# Design.net
KiCad netlist of a schematic drawn in EasyEDA
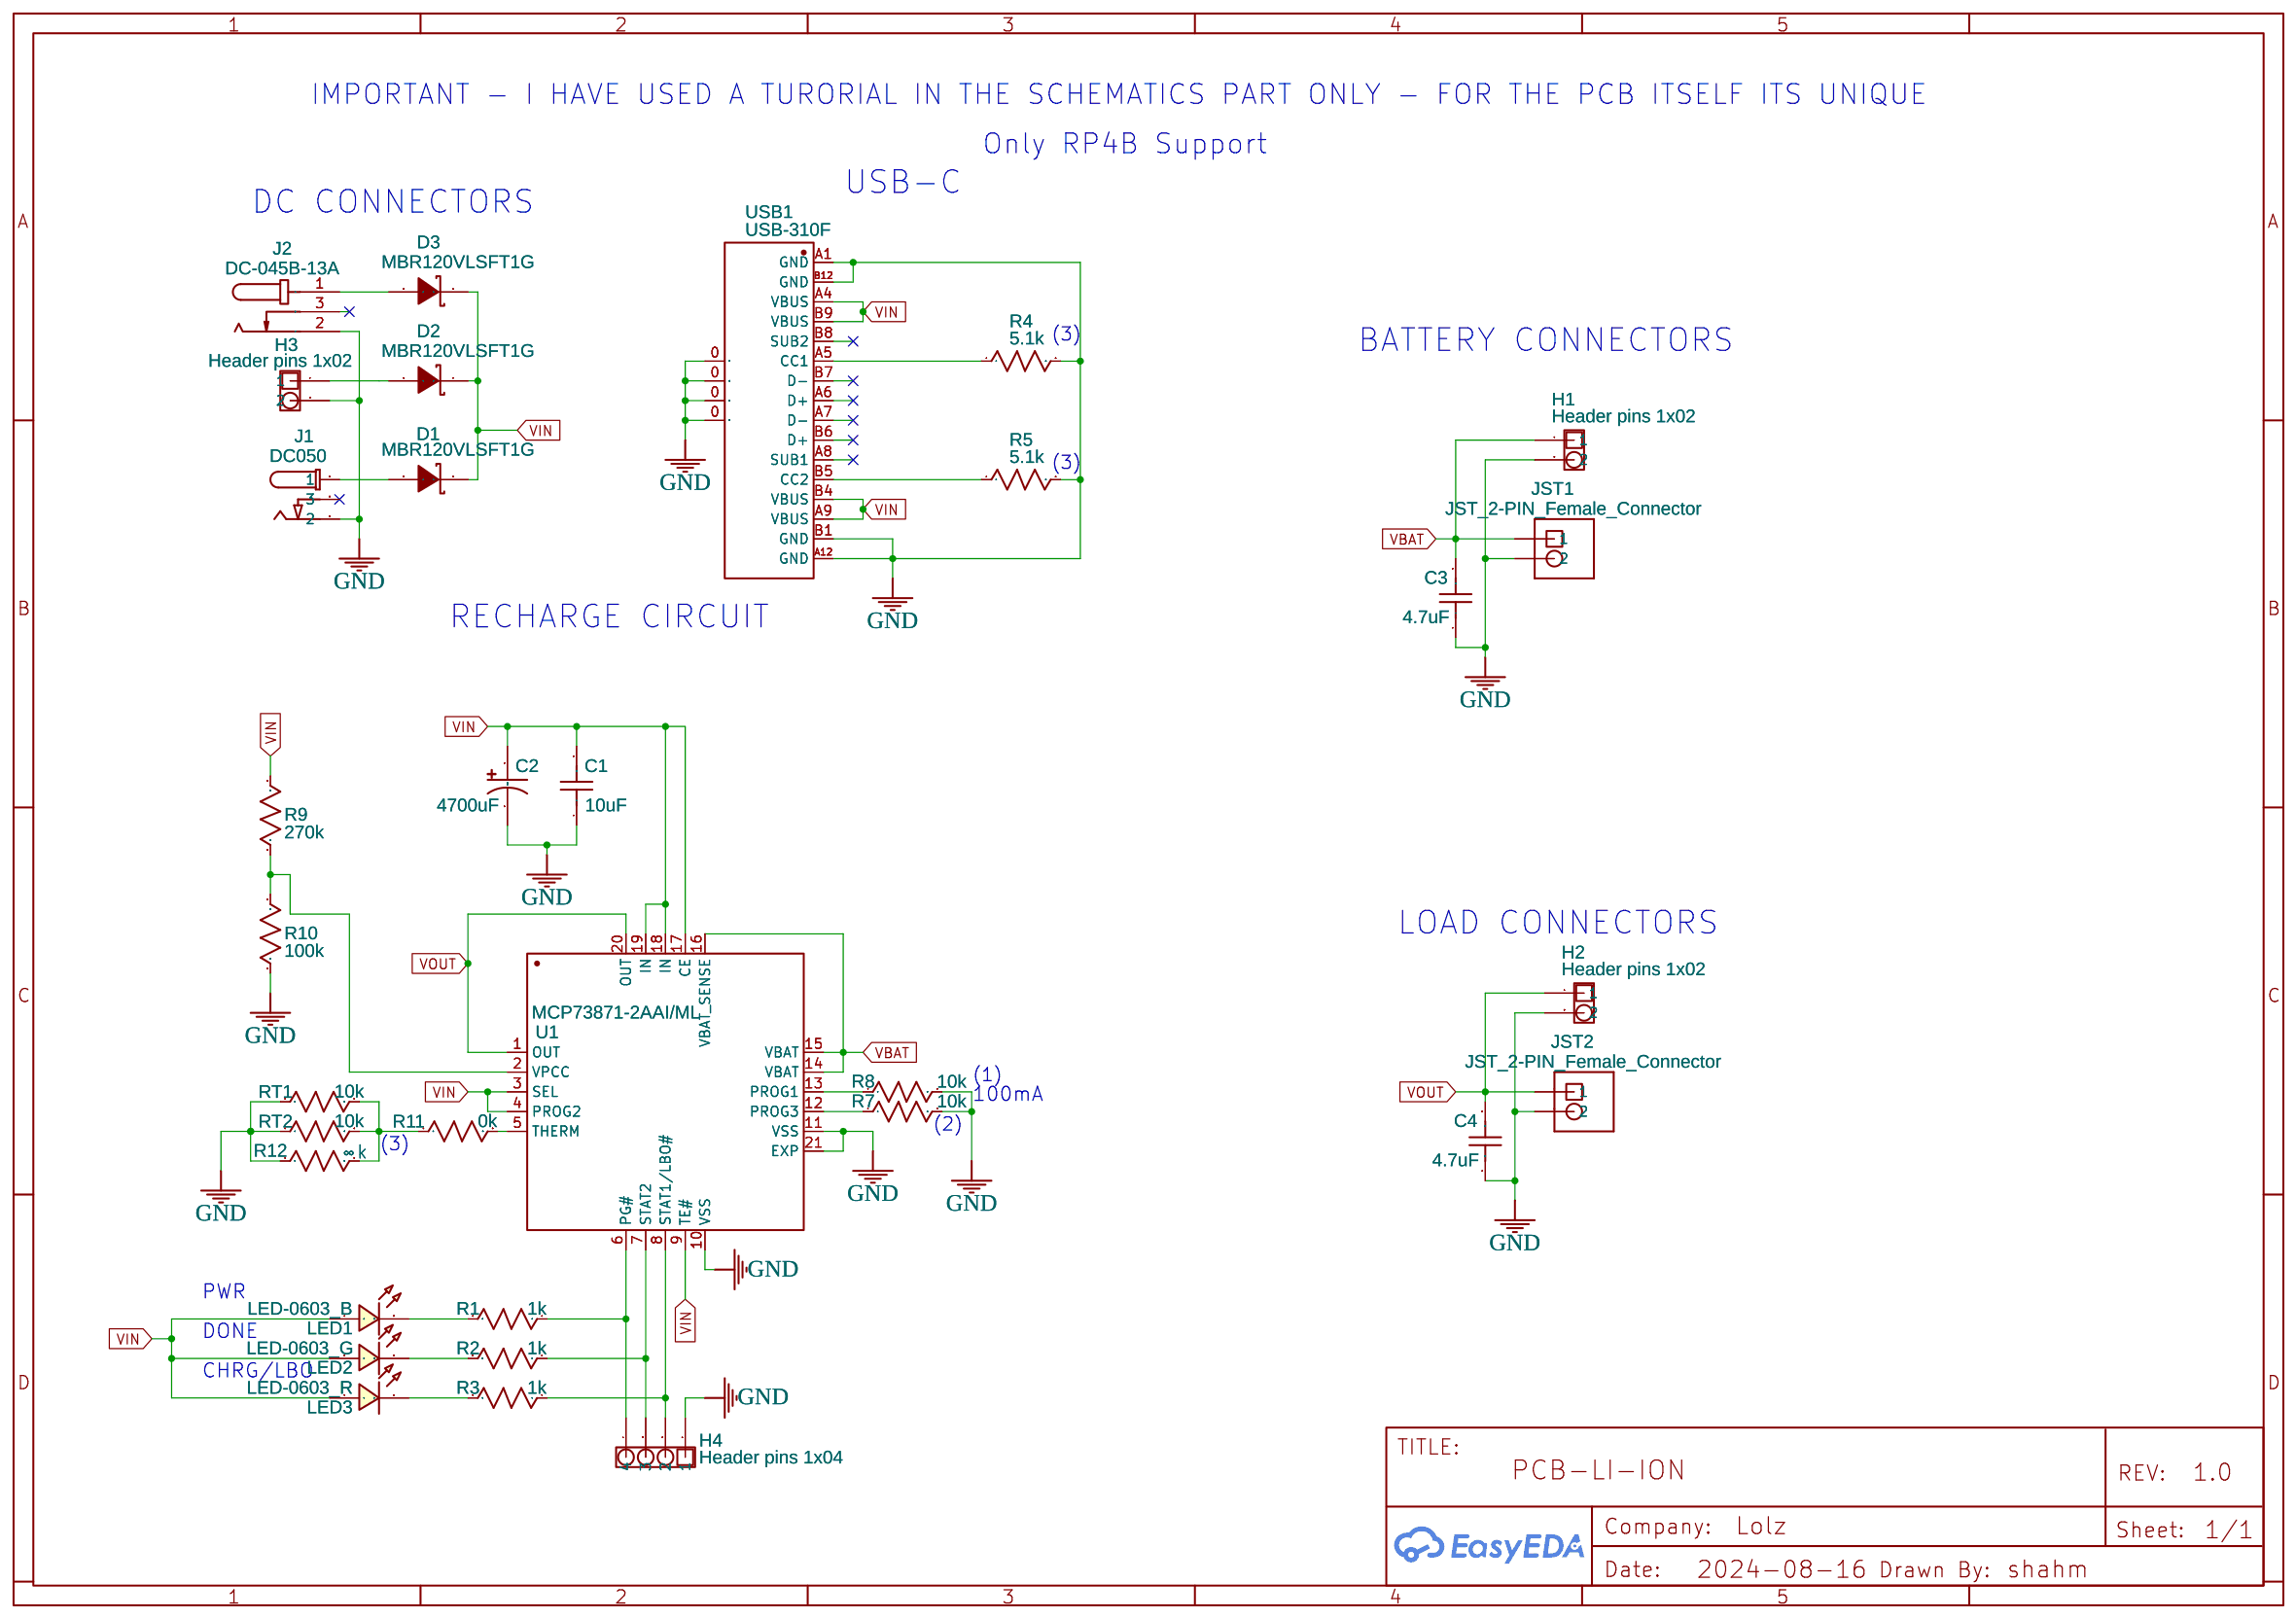
[diagram p0: schematic sheet]

(export (version "E")
  (design (tool "Eeschema 10.0.6"))
  (components
    (comp (ref "C1") (value "10uF") (libsource (lib "") (part "C_0603_US")))
    (comp (ref "C2")
      (value "4700uF")
      (fields (field (name "Manufacturer Part") "EEUFR1A472L") (field (name "Manufacturer") "PANASONIC"))
      (libsource (lib "") (part "EEUFR1A472L"))
    )
    (comp (ref "C3") (value "4.7uF") (libsource (lib "") (part "C_0603_US")))
    (comp (ref "C4") (value "4.7uF") (libsource (lib "") (part "C_0603_US")))
    (comp (ref "D1")
      (value "MBR120VLSFT1G")
      (fields (field (name "Manufacturer") "ON Semicon"))
      (libsource (lib "") (part "MBR120VLSFT1G"))
    )
    (comp (ref "D2")
      (value "MBR120VLSFT1G")
      (fields (field (name "Manufacturer") "ON Semicon"))
      (libsource (lib "") (part "MBR120VLSFT1G"))
    )
    (comp (ref "D3")
      (value "MBR120VLSFT1G")
      (fields (field (name "Manufacturer") "ON Semicon"))
      (libsource (lib "") (part "MBR120VLSFT1G"))
    )
    (comp (ref "H1") (value "Header pins 1x02") (libsource (lib "") (part "Header pins 1x02")))
    (comp (ref "H2") (value "Header pins 1x02") (libsource (lib "") (part "Header pins 1x02")))
    (comp (ref "H3") (value "Header pins 1x02") (libsource (lib "") (part "Header pins 1x02_1")))
    (comp (ref "H4") (value "Header pins 1x04") (libsource (lib "") (part "Header pins 1x04")))
    (comp (ref "J1")
      (value "DC050")
      (fields (field (name "Manufacturer Part") "DC00050-A") (field (name "Manufacturer") "SHOU HAN"))
      (libsource (lib "") (part "DC050 DC POWER CONNECTOR"))
    )
    (comp (ref "J2")
      (value "DC-045B-13A")
      (fields (field (name "Manufacturer") "HRO"))
      (libsource (lib "") (part "DC-045B-13A"))
    )
    (comp (ref "JST1")
      (value "JST_2-PIN_Female_Connector")
      (libsource (lib "") (part "JST_2-PIN_Female_Connector"))
    )
    (comp (ref "JST2")
      (value "JST_2-PIN_Female_Connector")
      (libsource (lib "") (part "JST_2-PIN_Female_Connector"))
    )
    (comp (ref "LED1")
      (value "LED-0603_B")
      (fields
        (field (name "Manufacturer Part") "19-217/BHC-ZL1M2RY/3T")
        (field (name "Manufacturer") "EVERLIGHT(台湾亿光)")
      )
      (libsource (lib "") (part "LED-0603_B"))
    )
    (comp (ref "LED2")
      (value "LED-0603_G")
      (fields
        (field (name "Manufacturer Part") "19-217/GHC-YR1S2/3T")
        (field (name "Manufacturer") "EVERLIGHT(台湾亿光)")
      )
      (libsource (lib "") (part "LED-0603_G"))
    )
    (comp (ref "LED3")
      (value "LED-0603_R")
      (fields
        (field (name "Manufacturer Part") "19-217/R6C-AL1M2VY/3T")
        (field (name "Manufacturer") "EVERLIGHT(台湾亿光)")
      )
      (libsource (lib "") (part "LED-0603_R"))
    )
    (comp (ref "R1") (value "1k") (libsource (lib "") (part "R_0603_US_2")))
    (comp (ref "R2") (value "1k") (libsource (lib "") (part "R_0603_US_2")))
    (comp (ref "R3") (value "1k") (libsource (lib "") (part "R_0603_US_2")))
    (comp (ref "R4") (value "5.1k") (libsource (lib "") (part "R_0603_US")))
    (comp (ref "R5") (value "5.1k") (libsource (lib "") (part "R_0603_US")))
    (comp (ref "R7") (value "10k") (libsource (lib "") (part "R_0603_US")))
    (comp (ref "R8") (value "10k") (libsource (lib "") (part "R_0603_US")))
    (comp (ref "R9") (value "270k") (libsource (lib "") (part "R_0603_US_3")))
    (comp (ref "R10") (value "100k") (libsource (lib "") (part "R_0603_US_3")))
    (comp (ref "R11") (value "0k") (libsource (lib "") (part "R_0603_US")))
    (comp (ref "R12") (value "∞k") (libsource (lib "") (part "R_0603_US")))
    (comp (ref "RT1") (value "10k") (libsource (lib "") (part "R_0603_US_1")))
    (comp (ref "RT2") (value "10k") (libsource (lib "") (part "R_0603_US_1")))
    (comp (ref "U1")
      (value "MCP73871-2AAI/ML")
      (fields (field (name "Manufacturer") "MICROCHIP"))
      (libsource (lib "") (part "MCP73871-2AAI/ML"))
    )
    (comp (ref "USB1")
      (value "USB-310F")
      (fields (field (name "Manufacturer") "HOOYA"))
      (libsource (lib "") (part "USB-310F"))
    )
  )
  (nets
    (net (code "1") (name "GND") (class "Default")
      (node (ref "C1") (pin "1") (pinfunction "1_1") (pintype "unspecified"))
      (node (ref "C2") (pin "2") (pinfunction "2_2") (pintype "unspecified"))
      (node (ref "C3") (pin "1") (pinfunction "1_1") (pintype "unspecified"))
      (node (ref "C4") (pin "1") (pinfunction "1_1") (pintype "unspecified"))
      (node (ref "H1") (pin "2") (pinfunction "2_2") (pintype "unspecified"))
      (node (ref "H2") (pin "2") (pinfunction "2_2") (pintype "unspecified"))
      (node (ref "H3") (pin "2") (pinfunction "2_2") (pintype "unspecified"))
      (node (ref "H4") (pin "1") (pinfunction "1_1") (pintype "unspecified"))
      (node (ref "J1") (pin "2") (pinfunction "2_2") (pintype "unspecified"))
      (node (ref "J2") (pin "2") (pinfunction "2_2") (pintype "unspecified"))
      (node (ref "JST1") (pin "2") (pinfunction "2_2") (pintype "unspecified"))
      (node (ref "JST2") (pin "2") (pinfunction "2_2") (pintype "unspecified"))
      (node (ref "R10") (pin "1") (pinfunction "1_1") (pintype "unspecified"))
      (node (ref "R12") (pin "1") (pinfunction "1_1") (pintype "unspecified"))
      (node (ref "R4") (pin "2") (pinfunction "2_2") (pintype "unspecified"))
      (node (ref "R5") (pin "2") (pinfunction "2_2") (pintype "unspecified"))
      (node (ref "R7") (pin "2") (pinfunction "2_2") (pintype "unspecified"))
      (node (ref "R8") (pin "2") (pinfunction "2_2") (pintype "unspecified"))
      (node (ref "RT1") (pin "1") (pinfunction "1_1") (pintype "unspecified"))
      (node (ref "RT2") (pin "1") (pinfunction "1_1") (pintype "unspecified"))
      (node (ref "U1") (pin "10") (pinfunction "VSS_10") (pintype "unspecified"))
      (node (ref "U1") (pin "11") (pinfunction "VSS_11") (pintype "unspecified"))
      (node (ref "U1") (pin "21") (pinfunction "EXP_21") (pintype "unspecified"))
      (node (ref "USB1") (pin "0") (pinfunction "0_0") (pintype "unspecified"))
      (node (ref "USB1") (pin "A1") (pinfunction "GND_A1") (pintype "unspecified"))
      (node (ref "USB1") (pin "A12") (pinfunction "GND_A12") (pintype "unspecified"))
      (node (ref "USB1") (pin "B1") (pinfunction "GND_B1") (pintype "unspecified"))
      (node (ref "USB1") (pin "B12") (pinfunction "GND_B12") (pintype "unspecified"))
    )
    (net (code "2") (name "Net-(D1-A)") (class "Default")
      (node (ref "D1") (pin "2") (pinfunction "A_2") (pintype "unspecified"))
      (node (ref "J1") (pin "1") (pinfunction "1_1") (pintype "unspecified"))
    )
    (net (code "3") (name "Net-(D2-A)") (class "Default")
      (node (ref "D2") (pin "2") (pinfunction "A_2") (pintype "unspecified"))
      (node (ref "H3") (pin "1") (pinfunction "1_1") (pintype "unspecified"))
    )
    (net (code "4") (name "Net-(D3-A)") (class "Default")
      (node (ref "D3") (pin "2") (pinfunction "A_2") (pintype "unspecified"))
      (node (ref "J2") (pin "1") (pinfunction "1_1") (pintype "unspecified"))
    )
    (net (code "5") (name "Net-(LED1-Pad2)") (class "Default")
      (node (ref "LED1") (pin "2") (pinfunction "2_2") (pintype "unspecified"))
      (node (ref "R1") (pin "2") (pinfunction "2_2") (pintype "unspecified"))
    )
    (net (code "6") (name "Net-(LED2-Pad2)") (class "Default")
      (node (ref "LED2") (pin "2") (pinfunction "2_2") (pintype "unspecified"))
      (node (ref "R2") (pin "2") (pinfunction "2_2") (pintype "unspecified"))
    )
    (net (code "7") (name "Net-(LED3-Pad2)") (class "Default")
      (node (ref "LED3") (pin "2") (pinfunction "2_2") (pintype "unspecified"))
      (node (ref "R3") (pin "2") (pinfunction "2_2") (pintype "unspecified"))
    )
    (net (code "8") (name "Net-(R11-Pad1)") (class "Default")
      (node (ref "R11") (pin "1") (pinfunction "1_1") (pintype "unspecified"))
      (node (ref "R12") (pin "2") (pinfunction "2_2") (pintype "unspecified"))
      (node (ref "RT1") (pin "2") (pinfunction "2_2") (pintype "unspecified"))
      (node (ref "RT2") (pin "2") (pinfunction "2_2") (pintype "unspecified"))
    )
    (net (code "9") (name "Net-(U1-PG#)") (class "Default")
      (node (ref "H4") (pin "4") (pinfunction "4_4") (pintype "unspecified"))
      (node (ref "R1") (pin "1") (pinfunction "1_1") (pintype "unspecified"))
      (node (ref "U1") (pin "6") (pinfunction "PG#_6") (pintype "unspecified"))
    )
    (net (code "10") (name "Net-(U1-PROG1)") (class "Default")
      (node (ref "R8") (pin "1") (pinfunction "1_1") (pintype "unspecified"))
      (node (ref "U1") (pin "13") (pinfunction "PROG1_13") (pintype "unspecified"))
    )
    (net (code "11") (name "Net-(U1-PROG3)") (class "Default")
      (node (ref "R7") (pin "1") (pinfunction "1_1") (pintype "unspecified"))
      (node (ref "U1") (pin "12") (pinfunction "PROG3_12") (pintype "unspecified"))
    )
    (net (code "12") (name "Net-(U1-STAT1{slash}LBO#)") (class "Default")
      (node (ref "H4") (pin "2") (pinfunction "2_2") (pintype "unspecified"))
      (node (ref "R3") (pin "1") (pinfunction "1_1") (pintype "unspecified"))
      (node (ref "U1") (pin "8") (pinfunction "STAT1/LBO#_8") (pintype "unspecified"))
    )
    (net (code "13") (name "Net-(U1-STAT2)") (class "Default")
      (node (ref "H4") (pin "3") (pinfunction "3_3") (pintype "unspecified"))
      (node (ref "R2") (pin "1") (pinfunction "1_1") (pintype "unspecified"))
      (node (ref "U1") (pin "7") (pinfunction "STAT2_7") (pintype "unspecified"))
    )
    (net (code "14") (name "Net-(U1-THERM)") (class "Default")
      (node (ref "R11") (pin "2") (pinfunction "2_2") (pintype "unspecified"))
      (node (ref "U1") (pin "5") (pinfunction "THERM_5") (pintype "unspecified"))
    )
    (net (code "15") (name "Net-(U1-VPCC)") (class "Default")
      (node (ref "R10") (pin "2") (pinfunction "2_2") (pintype "unspecified"))
      (node (ref "R9") (pin "1") (pinfunction "1_1") (pintype "unspecified"))
      (node (ref "U1") (pin "2") (pinfunction "VPCC_2") (pintype "unspecified"))
    )
    (net (code "16") (name "Net-(USB1-CC1)") (class "Default")
      (node (ref "R4") (pin "1") (pinfunction "1_1") (pintype "unspecified"))
      (node (ref "USB1") (pin "A5") (pinfunction "CC1_A5") (pintype "unspecified"))
    )
    (net (code "17") (name "Net-(USB1-CC2)") (class "Default")
      (node (ref "R5") (pin "1") (pinfunction "1_1") (pintype "unspecified"))
      (node (ref "USB1") (pin "B5") (pinfunction "CC2_B5") (pintype "unspecified"))
    )
    (net (code "18") (name "VBAT") (class "Default")
      (node (ref "C3") (pin "2") (pinfunction "2_2") (pintype "unspecified"))
      (node (ref "H1") (pin "1") (pinfunction "1_1") (pintype "unspecified"))
      (node (ref "JST1") (pin "1") (pinfunction "1_1") (pintype "unspecified"))
      (node (ref "U1") (pin "14") (pinfunction "VBAT_14") (pintype "unspecified"))
      (node (ref "U1") (pin "15") (pinfunction "VBAT_15") (pintype "unspecified"))
      (node (ref "U1") (pin "16") (pinfunction "VBAT_SENSE_16") (pintype "unspecified"))
    )
    (net (code "19") (name "VIN") (class "Default")
      (node (ref "C1") (pin "2") (pinfunction "2_2") (pintype "unspecified"))
      (node (ref "C2") (pin "1") (pinfunction "1_1") (pintype "unspecified"))
      (node (ref "D1") (pin "1") (pinfunction "K_1") (pintype "unspecified"))
      (node (ref "D2") (pin "1") (pinfunction "K_1") (pintype "unspecified"))
      (node (ref "D3") (pin "1") (pinfunction "K_1") (pintype "unspecified"))
      (node (ref "LED1") (pin "1") (pinfunction "1_1") (pintype "unspecified"))
      (node (ref "LED2") (pin "1") (pinfunction "1_1") (pintype "unspecified"))
      (node (ref "LED3") (pin "1") (pinfunction "1_1") (pintype "unspecified"))
      (node (ref "R9") (pin "2") (pinfunction "2_2") (pintype "unspecified"))
      (node (ref "U1") (pin "17") (pinfunction "CE_17") (pintype "unspecified"))
      (node (ref "U1") (pin "18") (pinfunction "IN_18") (pintype "unspecified"))
      (node (ref "U1") (pin "19") (pinfunction "IN_19") (pintype "unspecified"))
      (node (ref "U1") (pin "3") (pinfunction "SEL_3") (pintype "unspecified"))
      (node (ref "U1") (pin "4") (pinfunction "PROG2_4") (pintype "unspecified"))
      (node (ref "U1") (pin "9") (pinfunction "TE#_9") (pintype "unspecified"))
      (node (ref "USB1") (pin "A4") (pinfunction "VBUS_A4") (pintype "unspecified"))
      (node (ref "USB1") (pin "A9") (pinfunction "VBUS_A9") (pintype "unspecified"))
      (node (ref "USB1") (pin "B4") (pinfunction "VBUS_B4") (pintype "unspecified"))
      (node (ref "USB1") (pin "B9") (pinfunction "VBUS_B9") (pintype "unspecified"))
    )
    (net (code "20") (name "VOUT") (class "Default")
      (node (ref "C4") (pin "2") (pinfunction "2_2") (pintype "unspecified"))
      (node (ref "H2") (pin "1") (pinfunction "1_1") (pintype "unspecified"))
      (node (ref "JST2") (pin "1") (pinfunction "1_1") (pintype "unspecified"))
      (node (ref "U1") (pin "1") (pinfunction "OUT_1") (pintype "unspecified"))
      (node (ref "U1") (pin "20") (pinfunction "OUT_20") (pintype "unspecified"))
    )
    (net (code "21") (name "unconnected-(J1-Pad3)") (class "Default")
      (node (ref "J1") (pin "3") (pinfunction "3_3") (pintype "unspecified+no_connect"))
    )
    (net (code "22") (name "unconnected-(J2-Pad3)") (class "Default")
      (node (ref "J2") (pin "3") (pinfunction "3_3") (pintype "unspecified+no_connect"))
    )
    (net (code "23") (name "unconnected-(USB1-D+-PadA6)") (class "Default")
      (node (ref "USB1") (pin "A6") (pinfunction "D+_A6") (pintype "unspecified+no_connect"))
    )
    (net (code "24") (name "unconnected-(USB1-D+-PadB6)") (class "Default")
      (node (ref "USB1") (pin "B6") (pinfunction "D+_B6") (pintype "unspecified+no_connect"))
    )
    (net (code "25") (name "unconnected-(USB1-D--PadA7)") (class "Default")
      (node (ref "USB1") (pin "A7") (pinfunction "D-_A7") (pintype "unspecified+no_connect"))
    )
    (net (code "26") (name "unconnected-(USB1-D--PadB7)") (class "Default")
      (node (ref "USB1") (pin "B7") (pinfunction "D-_B7") (pintype "unspecified+no_connect"))
    )
    (net (code "27") (name "unconnected-(USB1-SUB1-PadA8)") (class "Default")
      (node (ref "USB1") (pin "A8") (pinfunction "SUB1_A8") (pintype "unspecified+no_connect"))
    )
    (net (code "28") (name "unconnected-(USB1-SUB2-PadB8)") (class "Default")
      (node (ref "USB1") (pin "B8") (pinfunction "SUB2_B8") (pintype "unspecified+no_connect"))
    )
  )
)
